# Protoboard_MX2-7-6-ESP12.net
KiCad netlist of a schematic drawn in EAGLE
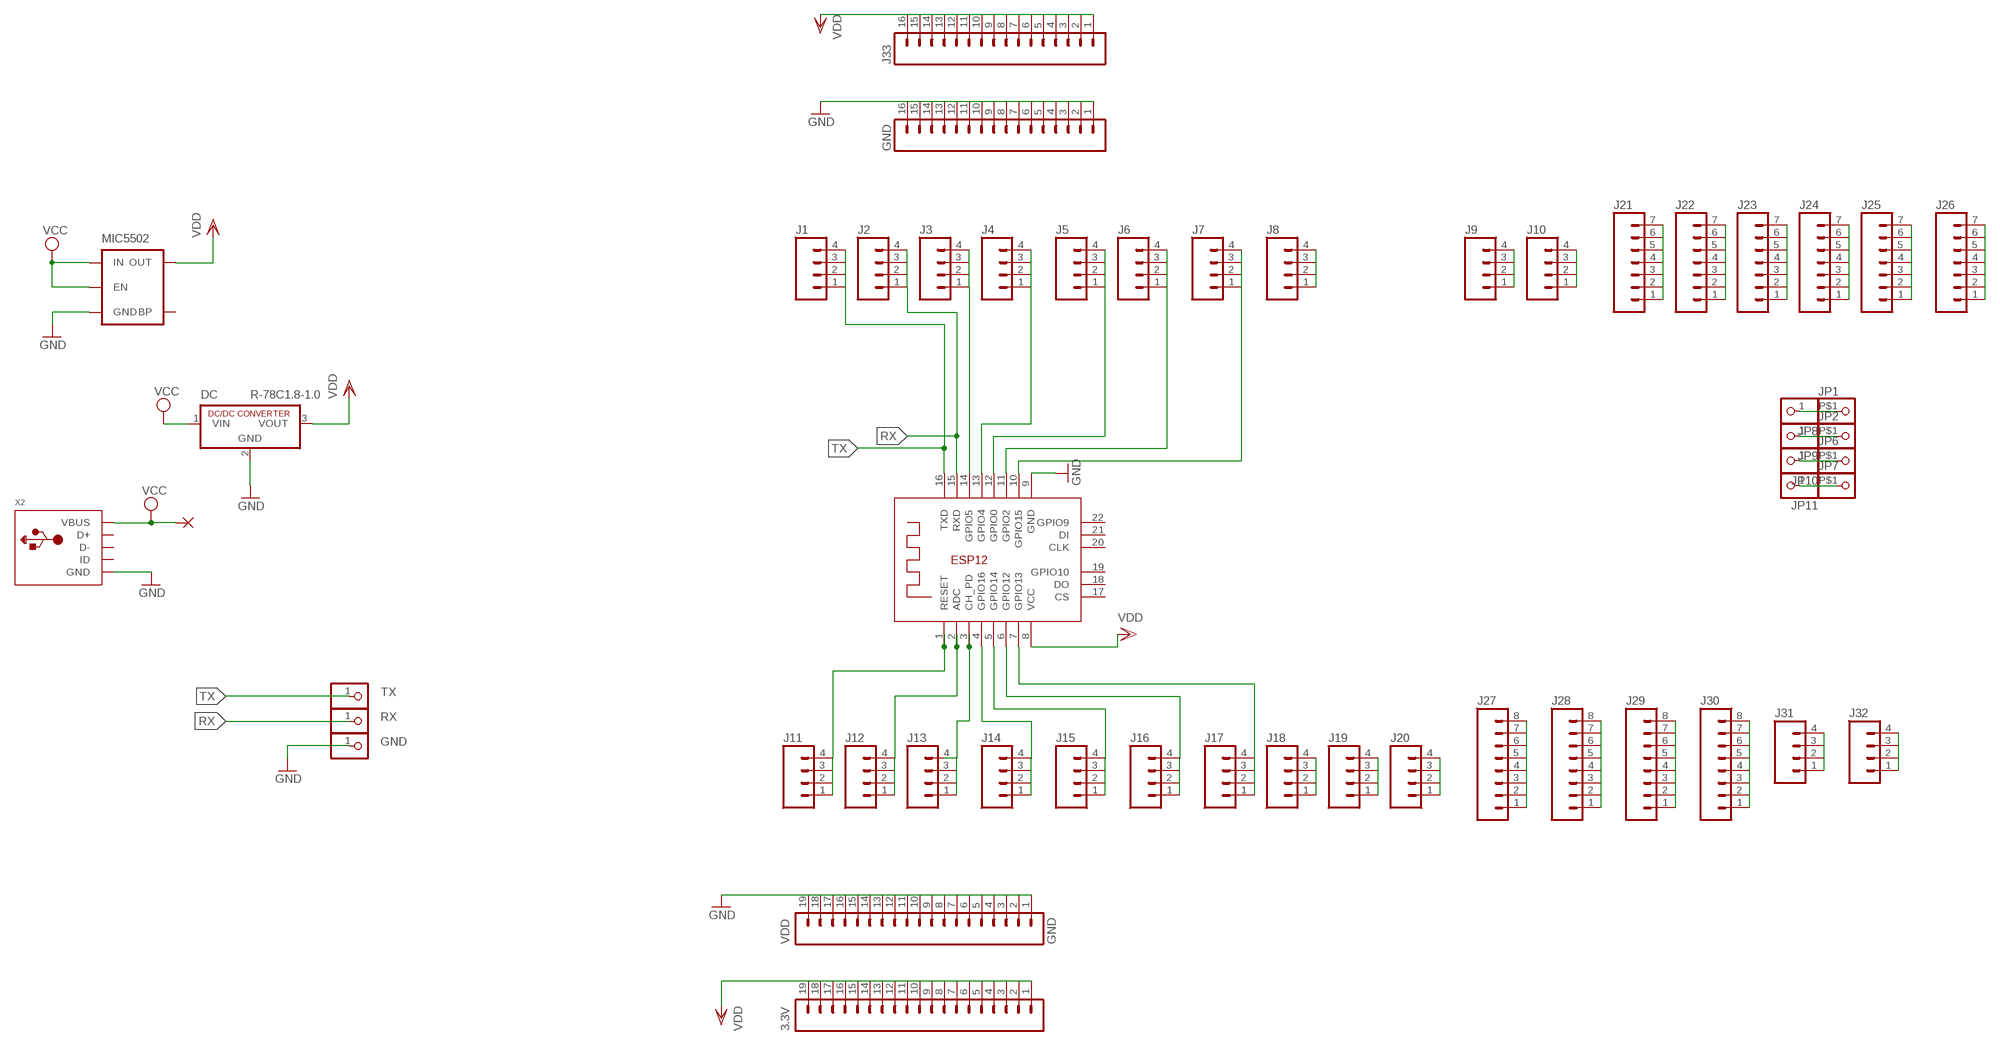
[diagram p0: schematic, sheet 1]

(export (version "E")
  (design (tool "Eeschema 10.0.6"))
  (components
    (comp (ref "3.3V")
      (value "M191X19_NO_SILK")
      (footprint "eagle-import:1X19_NO_SILK")
      (libsource (lib "eagle-import") (part "M191X19_NO_SILK"))
    )
    (comp (ref "5V")
      (value "1,6/0,8")
      (footprint "eagle-import:1,6_0,8")
      (libsource (lib "eagle-import") (part "1,6/0,8"))
    )
    (comp (ref "DC")
      (value "R-78C1.8-1.0")
      (footprint "eagle-import:SIP3")
      (libsource (lib "eagle-import") (part "R-78C-1.01.8"))
    )
    (comp (ref "GND")
      (value "M161X16_NO_SILK")
      (footprint "eagle-import:1X16_NO_SILK")
      (libsource (lib "eagle-import") (part "M161X16_NO_SILK"))
    )
    (comp (ref "J1")
      (value "M04NO_SILK_ALL_ROUND")
      (footprint "eagle-import:1X04_NO_SILK_ALL_ROUND")
      (libsource (lib "eagle-import") (part "M04NO_SILK_ALL_ROUND"))
    )
    (comp (ref "J2")
      (value "M04NO_SILK_ALL_ROUND")
      (footprint "eagle-import:1X04_NO_SILK_ALL_ROUND")
      (libsource (lib "eagle-import") (part "M04NO_SILK_ALL_ROUND"))
    )
    (comp (ref "J3")
      (value "M04NO_SILK_ALL_ROUND")
      (footprint "eagle-import:1X04_NO_SILK_ALL_ROUND")
      (libsource (lib "eagle-import") (part "M04NO_SILK_ALL_ROUND"))
    )
    (comp (ref "J4")
      (value "M04NO_SILK_ALL_ROUND")
      (footprint "eagle-import:1X04_NO_SILK_ALL_ROUND")
      (libsource (lib "eagle-import") (part "M04NO_SILK_ALL_ROUND"))
    )
    (comp (ref "J5")
      (value "M04NO_SILK_ALL_ROUND")
      (footprint "eagle-import:1X04_NO_SILK_ALL_ROUND")
      (libsource (lib "eagle-import") (part "M04NO_SILK_ALL_ROUND"))
    )
    (comp (ref "J6")
      (value "M04NO_SILK_ALL_ROUND")
      (footprint "eagle-import:1X04_NO_SILK_ALL_ROUND")
      (libsource (lib "eagle-import") (part "M04NO_SILK_ALL_ROUND"))
    )
    (comp (ref "J7")
      (value "M04NO_SILK_ALL_ROUND")
      (footprint "eagle-import:1X04_NO_SILK_ALL_ROUND")
      (libsource (lib "eagle-import") (part "M04NO_SILK_ALL_ROUND"))
    )
    (comp (ref "J8")
      (value "M04NO_SILK_ALL_ROUND")
      (footprint "eagle-import:1X04_NO_SILK_ALL_ROUND")
      (libsource (lib "eagle-import") (part "M04NO_SILK_ALL_ROUND"))
    )
    (comp (ref "J9")
      (value "M04NO_SILK_ALL_ROUND")
      (footprint "eagle-import:1X04_NO_SILK_ALL_ROUND")
      (libsource (lib "eagle-import") (part "M04NO_SILK_ALL_ROUND"))
    )
    (comp (ref "J10")
      (value "M04NO_SILK_ALL_ROUND")
      (footprint "eagle-import:1X04_NO_SILK_ALL_ROUND")
      (libsource (lib "eagle-import") (part "M04NO_SILK_ALL_ROUND"))
    )
    (comp (ref "J11")
      (value "M04NO_SILK_ALL_ROUND")
      (footprint "eagle-import:1X04_NO_SILK_ALL_ROUND")
      (libsource (lib "eagle-import") (part "M04NO_SILK_ALL_ROUND"))
    )
    (comp (ref "J12")
      (value "M04NO_SILK_ALL_ROUND")
      (footprint "eagle-import:1X04_NO_SILK_ALL_ROUND")
      (libsource (lib "eagle-import") (part "M04NO_SILK_ALL_ROUND"))
    )
    (comp (ref "J13")
      (value "M04NO_SILK_ALL_ROUND")
      (footprint "eagle-import:1X04_NO_SILK_ALL_ROUND")
      (libsource (lib "eagle-import") (part "M04NO_SILK_ALL_ROUND"))
    )
    (comp (ref "J14")
      (value "M04NO_SILK_ALL_ROUND")
      (footprint "eagle-import:1X04_NO_SILK_ALL_ROUND")
      (libsource (lib "eagle-import") (part "M04NO_SILK_ALL_ROUND"))
    )
    (comp (ref "J15")
      (value "M04NO_SILK_ALL_ROUND")
      (footprint "eagle-import:1X04_NO_SILK_ALL_ROUND")
      (libsource (lib "eagle-import") (part "M04NO_SILK_ALL_ROUND"))
    )
    (comp (ref "J16")
      (value "M04NO_SILK_ALL_ROUND")
      (footprint "eagle-import:1X04_NO_SILK_ALL_ROUND")
      (libsource (lib "eagle-import") (part "M04NO_SILK_ALL_ROUND"))
    )
    (comp (ref "J17")
      (value "M04NO_SILK_ALL_ROUND")
      (footprint "eagle-import:1X04_NO_SILK_ALL_ROUND")
      (libsource (lib "eagle-import") (part "M04NO_SILK_ALL_ROUND"))
    )
    (comp (ref "J18")
      (value "M04NO_SILK_ALL_ROUND")
      (footprint "eagle-import:1X04_NO_SILK_ALL_ROUND")
      (libsource (lib "eagle-import") (part "M04NO_SILK_ALL_ROUND"))
    )
    (comp (ref "J19")
      (value "M04NO_SILK_ALL_ROUND")
      (footprint "eagle-import:1X04_NO_SILK_ALL_ROUND")
      (libsource (lib "eagle-import") (part "M04NO_SILK_ALL_ROUND"))
    )
    (comp (ref "J20")
      (value "M04NO_SILK_ALL_ROUND")
      (footprint "eagle-import:1X04_NO_SILK_ALL_ROUND")
      (libsource (lib "eagle-import") (part "M04NO_SILK_ALL_ROUND"))
    )
    (comp (ref "J21")
      (value "M07NO_SILK")
      (footprint "eagle-import:1X07_NO_SILK")
      (libsource (lib "eagle-import") (part "M07NO_SILK"))
    )
    (comp (ref "J22")
      (value "M07NO_SILK")
      (footprint "eagle-import:1X07_NO_SILK")
      (libsource (lib "eagle-import") (part "M07NO_SILK"))
    )
    (comp (ref "J23")
      (value "M07NO_SILK")
      (footprint "eagle-import:1X07_NO_SILK")
      (libsource (lib "eagle-import") (part "M07NO_SILK"))
    )
    (comp (ref "J24")
      (value "M07NO_SILK")
      (footprint "eagle-import:1X07_NO_SILK")
      (libsource (lib "eagle-import") (part "M07NO_SILK"))
    )
    (comp (ref "J25")
      (value "M07NO_SILK")
      (footprint "eagle-import:1X07_NO_SILK")
      (libsource (lib "eagle-import") (part "M07NO_SILK"))
    )
    (comp (ref "J26")
      (value "M07NO_SILK")
      (footprint "eagle-import:1X07_NO_SILK")
      (libsource (lib "eagle-import") (part "M07NO_SILK"))
    )
    (comp (ref "J27")
      (value "M08NO_SILK_FEMALE_PTH")
      (footprint "eagle-import:1X08_NO_SILK")
      (libsource (lib "eagle-import") (part "M08NO_SILK_FEMALE_PTH"))
    )
    (comp (ref "J28")
      (value "M08NO_SILK_FEMALE_PTH")
      (footprint "eagle-import:1X08_NO_SILK")
      (libsource (lib "eagle-import") (part "M08NO_SILK_FEMALE_PTH"))
    )
    (comp (ref "J29")
      (value "M08NO_SILK_FEMALE_PTH")
      (footprint "eagle-import:1X08_NO_SILK")
      (libsource (lib "eagle-import") (part "M08NO_SILK_FEMALE_PTH"))
    )
    (comp (ref "J30")
      (value "M08NO_SILK_FEMALE_PTH")
      (footprint "eagle-import:1X08_NO_SILK")
      (libsource (lib "eagle-import") (part "M08NO_SILK_FEMALE_PTH"))
    )
    (comp (ref "J31")
      (value "M04NO_SILK_ALL_ROUND")
      (footprint "eagle-import:1X04_NO_SILK_ALL_ROUND")
      (libsource (lib "eagle-import") (part "M04NO_SILK_ALL_ROUND"))
    )
    (comp (ref "J32")
      (value "M04NO_SILK_ALL_ROUND")
      (footprint "eagle-import:1X04_NO_SILK_ALL_ROUND")
      (libsource (lib "eagle-import") (part "M04NO_SILK_ALL_ROUND"))
    )
    (comp (ref "J33")
      (value "M161X16_NO_SILK")
      (footprint "eagle-import:1X16_NO_SILK")
      (libsource (lib "eagle-import") (part "M161X16_NO_SILK"))
    )
    (comp (ref "JP1")
      (value "PINHD-1X1-BIGPOGO")
      (footprint "eagle-import:1X1-BIGPOGO")
      (libsource (lib "eagle-import") (part "PINHD-1X1-BIGPOGO"))
    )
    (comp (ref "JP2")
      (value "PINHD-1X1-BIGPOGO")
      (footprint "eagle-import:1X1-BIGPOGO")
      (libsource (lib "eagle-import") (part "PINHD-1X1-BIGPOGO"))
    )
    (comp (ref "JP3")
      (value "TX")
      (footprint "eagle-import:1X01-CLEANBIG")
      (libsource (lib "eagle-import") (part "PINHD-1X1CB"))
    )
    (comp (ref "JP4")
      (value "RX")
      (footprint "eagle-import:1X01-CLEANBIG")
      (libsource (lib "eagle-import") (part "PINHD-1X1CB"))
    )
    (comp (ref "JP5")
      (value "GND")
      (footprint "eagle-import:1X01-CLEANBIG")
      (libsource (lib "eagle-import") (part "PINHD-1X1CB"))
    )
    (comp (ref "JP6")
      (value "PINHD-1X1-BIGPOGO")
      (footprint "eagle-import:1X1-BIGPOGO")
      (libsource (lib "eagle-import") (part "PINHD-1X1-BIGPOGO"))
    )
    (comp (ref "JP7")
      (value "PINHD-1X1-BIGPOGO")
      (footprint "eagle-import:1X1-BIGPOGO")
      (libsource (lib "eagle-import") (part "PINHD-1X1-BIGPOGO"))
    )
    (comp (ref "JP8")
      (value "PINHD-1X1CB")
      (footprint "eagle-import:1X01-CLEANBIG")
      (libsource (lib "eagle-import") (part "PINHD-1X1CB"))
    )
    (comp (ref "JP9")
      (value "PINHD-1X1CB")
      (footprint "eagle-import:1X01-CLEANBIG")
      (libsource (lib "eagle-import") (part "PINHD-1X1CB"))
    )
    (comp (ref "JP10")
      (value "PINHD-1X1CB")
      (footprint "eagle-import:1X01-CLEANBIG")
      (libsource (lib "eagle-import") (part "PINHD-1X1CB"))
    )
    (comp (ref "JP11")
      (value "PINHD-1X1CB")
      (footprint "eagle-import:1X01-CLEANBIG")
      (libsource (lib "eagle-import") (part "PINHD-1X1CB"))
    )
    (comp (ref "MIC5502")
      (value "MIC52053.3V")
      (footprint "eagle-import:SOT23-5")
      (libsource (lib "eagle-import") (part "MIC52053.3V"))
    )
    (comp (ref "VDD")
      (value "GND")
      (footprint "eagle-import:1X19_NO_SILK")
      (libsource (lib "eagle-import") (part "M191X19_NO_SILK"))
    )
    (comp (ref "X1")
      (value "ESP-12E")
      (footprint "eagle-import:ESP-12E")
      (libsource (lib "eagle-import") (part "ESP-12E"))
    )
    (comp (ref "X2")
      (value "USBMICRO_20329")
      (footprint "eagle-import:4UCONN_20329")
      (libsource (lib "eagle-import") (part "USBMICRO_20329"))
    )
  )
  (nets
    (net (code "1") (name "GND") (class "Default")
      (node (ref "DC") (pin "2") (pinfunction "GND_2") (pintype "passive"))
      (node (ref "GND") (pin "1") (pinfunction "1_1") (pintype "passive"))
      (node (ref "GND") (pin "10") (pinfunction "10_10") (pintype "passive"))
      (node (ref "GND") (pin "11") (pinfunction "11_11") (pintype "passive"))
      (node (ref "GND") (pin "12") (pinfunction "12_12") (pintype "passive"))
      (node (ref "GND") (pin "13") (pinfunction "13_13") (pintype "passive"))
      (node (ref "GND") (pin "14") (pinfunction "14_14") (pintype "passive"))
      (node (ref "GND") (pin "15") (pinfunction "15_15") (pintype "passive"))
      (node (ref "GND") (pin "16") (pinfunction "16_16") (pintype "passive"))
      (node (ref "GND") (pin "2") (pinfunction "2_2") (pintype "passive"))
      (node (ref "GND") (pin "3") (pinfunction "3_3") (pintype "passive"))
      (node (ref "GND") (pin "4") (pinfunction "4_4") (pintype "passive"))
      (node (ref "GND") (pin "5") (pinfunction "5_5") (pintype "passive"))
      (node (ref "GND") (pin "6") (pinfunction "6_6") (pintype "passive"))
      (node (ref "GND") (pin "7") (pinfunction "7_7") (pintype "passive"))
      (node (ref "GND") (pin "8") (pinfunction "8_8") (pintype "passive"))
      (node (ref "GND") (pin "9") (pinfunction "9_9") (pintype "passive"))
      (node (ref "JP5") (pin "1") (pinfunction "1_1") (pintype "passive"))
      (node (ref "MIC5502") (pin "2") (pinfunction "GND_2") (pintype "input"))
      (node (ref "VDD") (pin "1") (pinfunction "1_1") (pintype "passive"))
      (node (ref "VDD") (pin "10") (pinfunction "10_10") (pintype "passive"))
      (node (ref "VDD") (pin "11") (pinfunction "11_11") (pintype "passive"))
      (node (ref "VDD") (pin "12") (pinfunction "12_12") (pintype "passive"))
      (node (ref "VDD") (pin "13") (pinfunction "13_13") (pintype "passive"))
      (node (ref "VDD") (pin "14") (pinfunction "14_14") (pintype "passive"))
      (node (ref "VDD") (pin "15") (pinfunction "15_15") (pintype "passive"))
      (node (ref "VDD") (pin "16") (pinfunction "16_16") (pintype "passive"))
      (node (ref "VDD") (pin "17") (pinfunction "17_17") (pintype "passive"))
      (node (ref "VDD") (pin "18") (pinfunction "18_18") (pintype "passive"))
      (node (ref "VDD") (pin "19") (pinfunction "19_19") (pintype "passive"))
      (node (ref "VDD") (pin "2") (pinfunction "2_2") (pintype "passive"))
      (node (ref "VDD") (pin "3") (pinfunction "3_3") (pintype "passive"))
      (node (ref "VDD") (pin "4") (pinfunction "4_4") (pintype "passive"))
      (node (ref "VDD") (pin "5") (pinfunction "5_5") (pintype "passive"))
      (node (ref "VDD") (pin "6") (pinfunction "6_6") (pintype "passive"))
      (node (ref "VDD") (pin "7") (pinfunction "7_7") (pintype "passive"))
      (node (ref "VDD") (pin "8") (pinfunction "8_8") (pintype "passive"))
      (node (ref "VDD") (pin "9") (pinfunction "9_9") (pintype "passive"))
      (node (ref "X1") (pin "9") (pinfunction "GND_9") (pintype "power_in"))
      (node (ref "X2") (pin "BASE@1") (pinfunction "GND_BASE@1") (pintype "power_in"))
      (node (ref "X2") (pin "BASE@2") (pinfunction "GND_BASE@2") (pintype "power_in"))
      (node (ref "X2") (pin "GND") (pinfunction "GND_GND") (pintype "power_in"))
      (node (ref "X2") (pin "SPRT@1") (pinfunction "GND_SPRT@1") (pintype "power_in"))
      (node (ref "X2") (pin "SPRT@2") (pinfunction "GND_SPRT@2") (pintype "power_in"))
      (node (ref "X2") (pin "SPRT@3") (pinfunction "GND_SPRT@3") (pintype "power_in"))
      (node (ref "X2") (pin "SPRT@4") (pinfunction "GND_SPRT@4") (pintype "power_in"))
    )
    (net (code "2") (name "Net-(J8-Pad1)") (class "Default")
      (node (ref "J8") (pin "1") (pinfunction "1_1") (pintype "passive"))
      (node (ref "J8") (pin "2") (pinfunction "2_2") (pintype "passive"))
      (node (ref "J8") (pin "3") (pinfunction "3_3") (pintype "passive"))
      (node (ref "J8") (pin "4") (pinfunction "4_4") (pintype "passive"))
    )
    (net (code "3") (name "Net-(J9-Pad1)") (class "Default")
      (node (ref "J9") (pin "1") (pinfunction "1_1") (pintype "passive"))
      (node (ref "J9") (pin "2") (pinfunction "2_2") (pintype "passive"))
      (node (ref "J9") (pin "3") (pinfunction "3_3") (pintype "passive"))
      (node (ref "J9") (pin "4") (pinfunction "4_4") (pintype "passive"))
    )
    (net (code "4") (name "Net-(J10-Pad1)") (class "Default")
      (node (ref "J10") (pin "1") (pinfunction "1_1") (pintype "passive"))
      (node (ref "J10") (pin "2") (pinfunction "2_2") (pintype "passive"))
      (node (ref "J10") (pin "3") (pinfunction "3_3") (pintype "passive"))
      (node (ref "J10") (pin "4") (pinfunction "4_4") (pintype "passive"))
    )
    (net (code "5") (name "Net-(J18-Pad1)") (class "Default")
      (node (ref "J18") (pin "1") (pinfunction "1_1") (pintype "passive"))
      (node (ref "J18") (pin "2") (pinfunction "2_2") (pintype "passive"))
      (node (ref "J18") (pin "3") (pinfunction "3_3") (pintype "passive"))
      (node (ref "J18") (pin "4") (pinfunction "4_4") (pintype "passive"))
    )
    (net (code "6") (name "Net-(J19-Pad1)") (class "Default")
      (node (ref "J19") (pin "1") (pinfunction "1_1") (pintype "passive"))
      (node (ref "J19") (pin "2") (pinfunction "2_2") (pintype "passive"))
      (node (ref "J19") (pin "3") (pinfunction "3_3") (pintype "passive"))
      (node (ref "J19") (pin "4") (pinfunction "4_4") (pintype "passive"))
    )
    (net (code "7") (name "Net-(J20-Pad1)") (class "Default")
      (node (ref "J20") (pin "1") (pinfunction "1_1") (pintype "passive"))
      (node (ref "J20") (pin "2") (pinfunction "2_2") (pintype "passive"))
      (node (ref "J20") (pin "3") (pinfunction "3_3") (pintype "passive"))
      (node (ref "J20") (pin "4") (pinfunction "4_4") (pintype "passive"))
    )
    (net (code "8") (name "Net-(J21-Pad1)") (class "Default")
      (node (ref "J21") (pin "1") (pinfunction "1_1") (pintype "passive"))
      (node (ref "J21") (pin "2") (pinfunction "2_2") (pintype "passive"))
      (node (ref "J21") (pin "3") (pinfunction "3_3") (pintype "passive"))
      (node (ref "J21") (pin "4") (pinfunction "4_4") (pintype "passive"))
      (node (ref "J21") (pin "5") (pinfunction "5_5") (pintype "passive"))
      (node (ref "J21") (pin "6") (pinfunction "6_6") (pintype "passive"))
      (node (ref "J21") (pin "7") (pinfunction "7_7") (pintype "passive"))
    )
    (net (code "9") (name "Net-(J22-Pad1)") (class "Default")
      (node (ref "J22") (pin "1") (pinfunction "1_1") (pintype "passive"))
      (node (ref "J22") (pin "2") (pinfunction "2_2") (pintype "passive"))
      (node (ref "J22") (pin "3") (pinfunction "3_3") (pintype "passive"))
      (node (ref "J22") (pin "4") (pinfunction "4_4") (pintype "passive"))
      (node (ref "J22") (pin "5") (pinfunction "5_5") (pintype "passive"))
      (node (ref "J22") (pin "6") (pinfunction "6_6") (pintype "passive"))
      (node (ref "J22") (pin "7") (pinfunction "7_7") (pintype "passive"))
    )
    (net (code "10") (name "Net-(J23-Pad1)") (class "Default")
      (node (ref "J23") (pin "1") (pinfunction "1_1") (pintype "passive"))
      (node (ref "J23") (pin "2") (pinfunction "2_2") (pintype "passive"))
      (node (ref "J23") (pin "3") (pinfunction "3_3") (pintype "passive"))
      (node (ref "J23") (pin "4") (pinfunction "4_4") (pintype "passive"))
      (node (ref "J23") (pin "5") (pinfunction "5_5") (pintype "passive"))
      (node (ref "J23") (pin "6") (pinfunction "6_6") (pintype "passive"))
      (node (ref "J23") (pin "7") (pinfunction "7_7") (pintype "passive"))
    )
    (net (code "11") (name "Net-(J24-Pad1)") (class "Default")
      (node (ref "J24") (pin "1") (pinfunction "1_1") (pintype "passive"))
      (node (ref "J24") (pin "2") (pinfunction "2_2") (pintype "passive"))
      (node (ref "J24") (pin "3") (pinfunction "3_3") (pintype "passive"))
      (node (ref "J24") (pin "4") (pinfunction "4_4") (pintype "passive"))
      (node (ref "J24") (pin "5") (pinfunction "5_5") (pintype "passive"))
      (node (ref "J24") (pin "6") (pinfunction "6_6") (pintype "passive"))
      (node (ref "J24") (pin "7") (pinfunction "7_7") (pintype "passive"))
    )
    (net (code "12") (name "Net-(J25-Pad1)") (class "Default")
      (node (ref "J25") (pin "1") (pinfunction "1_1") (pintype "passive"))
      (node (ref "J25") (pin "2") (pinfunction "2_2") (pintype "passive"))
      (node (ref "J25") (pin "3") (pinfunction "3_3") (pintype "passive"))
      (node (ref "J25") (pin "4") (pinfunction "4_4") (pintype "passive"))
      (node (ref "J25") (pin "5") (pinfunction "5_5") (pintype "passive"))
      (node (ref "J25") (pin "6") (pinfunction "6_6") (pintype "passive"))
      (node (ref "J25") (pin "7") (pinfunction "7_7") (pintype "passive"))
    )
    (net (code "13") (name "Net-(J26-Pad1)") (class "Default")
      (node (ref "J26") (pin "1") (pinfunction "1_1") (pintype "passive"))
      (node (ref "J26") (pin "2") (pinfunction "2_2") (pintype "passive"))
      (node (ref "J26") (pin "3") (pinfunction "3_3") (pintype "passive"))
      (node (ref "J26") (pin "4") (pinfunction "4_4") (pintype "passive"))
      (node (ref "J26") (pin "5") (pinfunction "5_5") (pintype "passive"))
      (node (ref "J26") (pin "6") (pinfunction "6_6") (pintype "passive"))
      (node (ref "J26") (pin "7") (pinfunction "7_7") (pintype "passive"))
    )
    (net (code "14") (name "Net-(J27-Pad1)") (class "Default")
      (node (ref "J27") (pin "1") (pinfunction "1_1") (pintype "passive"))
      (node (ref "J27") (pin "2") (pinfunction "2_2") (pintype "passive"))
      (node (ref "J27") (pin "3") (pinfunction "3_3") (pintype "passive"))
      (node (ref "J27") (pin "4") (pinfunction "4_4") (pintype "passive"))
      (node (ref "J27") (pin "5") (pinfunction "5_5") (pintype "passive"))
      (node (ref "J27") (pin "6") (pinfunction "6_6") (pintype "passive"))
      (node (ref "J27") (pin "7") (pinfunction "7_7") (pintype "passive"))
      (node (ref "J27") (pin "8") (pinfunction "8_8") (pintype "passive"))
    )
    (net (code "15") (name "Net-(J28-Pad1)") (class "Default")
      (node (ref "J28") (pin "1") (pinfunction "1_1") (pintype "passive"))
      (node (ref "J28") (pin "2") (pinfunction "2_2") (pintype "passive"))
      (node (ref "J28") (pin "3") (pinfunction "3_3") (pintype "passive"))
      (node (ref "J28") (pin "4") (pinfunction "4_4") (pintype "passive"))
      (node (ref "J28") (pin "5") (pinfunction "5_5") (pintype "passive"))
      (node (ref "J28") (pin "6") (pinfunction "6_6") (pintype "passive"))
      (node (ref "J28") (pin "7") (pinfunction "7_7") (pintype "passive"))
      (node (ref "J28") (pin "8") (pinfunction "8_8") (pintype "passive"))
    )
    (net (code "16") (name "Net-(J29-Pad1)") (class "Default")
      (node (ref "J29") (pin "1") (pinfunction "1_1") (pintype "passive"))
      (node (ref "J29") (pin "2") (pinfunction "2_2") (pintype "passive"))
      (node (ref "J29") (pin "3") (pinfunction "3_3") (pintype "passive"))
      (node (ref "J29") (pin "4") (pinfunction "4_4") (pintype "passive"))
      (node (ref "J29") (pin "5") (pinfunction "5_5") (pintype "passive"))
      (node (ref "J29") (pin "6") (pinfunction "6_6") (pintype "passive"))
      (node (ref "J29") (pin "7") (pinfunction "7_7") (pintype "passive"))
      (node (ref "J29") (pin "8") (pinfunction "8_8") (pintype "passive"))
    )
    (net (code "17") (name "Net-(J30-Pad1)") (class "Default")
      (node (ref "J30") (pin "1") (pinfunction "1_1") (pintype "passive"))
      (node (ref "J30") (pin "2") (pinfunction "2_2") (pintype "passive"))
      (node (ref "J30") (pin "3") (pinfunction "3_3") (pintype "passive"))
      (node (ref "J30") (pin "4") (pinfunction "4_4") (pintype "passive"))
      (node (ref "J30") (pin "5") (pinfunction "5_5") (pintype "passive"))
      (node (ref "J30") (pin "6") (pinfunction "6_6") (pintype "passive"))
      (node (ref "J30") (pin "7") (pinfunction "7_7") (pintype "passive"))
      (node (ref "J30") (pin "8") (pinfunction "8_8") (pintype "passive"))
    )
    (net (code "18") (name "Net-(J31-Pad1)") (class "Default")
      (node (ref "J31") (pin "1") (pinfunction "1_1") (pintype "passive"))
      (node (ref "J31") (pin "2") (pinfunction "2_2") (pintype "passive"))
      (node (ref "J31") (pin "3") (pinfunction "3_3") (pintype "passive"))
      (node (ref "J31") (pin "4") (pinfunction "4_4") (pintype "passive"))
    )
    (net (code "19") (name "Net-(J32-Pad1)") (class "Default")
      (node (ref "J32") (pin "1") (pinfunction "1_1") (pintype "passive"))
      (node (ref "J32") (pin "2") (pinfunction "2_2") (pintype "passive"))
      (node (ref "J32") (pin "3") (pinfunction "3_3") (pintype "passive"))
      (node (ref "J32") (pin "4") (pinfunction "4_4") (pintype "passive"))
    )
    (net (code "20") (name "Net-(JP1-1)") (class "Default")
      (node (ref "JP1") (pin "P$1") (pinfunction "1_P$1") (pintype "passive"))
      (node (ref "JP8") (pin "1") (pinfunction "1_1") (pintype "passive"))
    )
    (net (code "21") (name "Net-(JP2-1)") (class "Default")
      (node (ref "JP2") (pin "P$1") (pinfunction "1_P$1") (pintype "passive"))
      (node (ref "JP9") (pin "1") (pinfunction "1_1") (pintype "passive"))
    )
    (net (code "22") (name "Net-(JP6-1)") (class "Default")
      (node (ref "JP10") (pin "1") (pinfunction "1_1") (pintype "passive"))
      (node (ref "JP6") (pin "P$1") (pinfunction "1_P$1") (pintype "passive"))
    )
    (net (code "23") (name "Net-(JP7-1)") (class "Default")
      (node (ref "JP11") (pin "1") (pinfunction "1_1") (pintype "passive"))
      (node (ref "JP7") (pin "P$1") (pinfunction "1_P$1") (pintype "passive"))
    )
    (net (code "24") (name "Net-(X1-ADC)") (class "Default")
      (node (ref "J12") (pin "1") (pinfunction "1_1") (pintype "passive"))
      (node (ref "J12") (pin "2") (pinfunction "2_2") (pintype "passive"))
      (node (ref "J12") (pin "3") (pinfunction "3_3") (pintype "passive"))
      (node (ref "J12") (pin "4") (pinfunction "4_4") (pintype "passive"))
      (node (ref "X1") (pin "2") (pinfunction "ADC_2") (pintype "passive"))
    )
    (net (code "25") (name "Net-(X1-CH_PD)") (class "Default")
      (node (ref "J13") (pin "1") (pinfunction "1_1") (pintype "passive"))
      (node (ref "J13") (pin "2") (pinfunction "2_2") (pintype "passive"))
      (node (ref "J13") (pin "3") (pinfunction "3_3") (pintype "passive"))
      (node (ref "J13") (pin "4") (pinfunction "4_4") (pintype "passive"))
      (node (ref "X1") (pin "3") (pinfunction "CH_PD_3") (pintype "input"))
    )
    (net (code "26") (name "Net-(X1-GPIO0)") (class "Default")
      (node (ref "J5") (pin "1") (pinfunction "1_1") (pintype "passive"))
      (node (ref "J5") (pin "2") (pinfunction "2_2") (pintype "passive"))
      (node (ref "J5") (pin "3") (pinfunction "3_3") (pintype "passive"))
      (node (ref "J5") (pin "4") (pinfunction "4_4") (pintype "passive"))
      (node (ref "X1") (pin "12") (pinfunction "GPIO0_12") (pintype "bidirectional"))
    )
    (net (code "27") (name "Net-(X1-GPIO2)") (class "Default")
      (node (ref "J6") (pin "1") (pinfunction "1_1") (pintype "passive"))
      (node (ref "J6") (pin "2") (pinfunction "2_2") (pintype "passive"))
      (node (ref "J6") (pin "3") (pinfunction "3_3") (pintype "passive"))
      (node (ref "J6") (pin "4") (pinfunction "4_4") (pintype "passive"))
      (node (ref "X1") (pin "11") (pinfunction "GPIO2_11") (pintype "bidirectional"))
    )
    (net (code "28") (name "Net-(X1-GPIO4)") (class "Default")
      (node (ref "J4") (pin "1") (pinfunction "1_1") (pintype "passive"))
      (node (ref "J4") (pin "2") (pinfunction "2_2") (pintype "passive"))
      (node (ref "J4") (pin "3") (pinfunction "3_3") (pintype "passive"))
      (node (ref "J4") (pin "4") (pinfunction "4_4") (pintype "passive"))
      (node (ref "X1") (pin "13") (pinfunction "GPIO4_13") (pintype "bidirectional"))
    )
    (net (code "29") (name "Net-(X1-GPIO5)") (class "Default")
      (node (ref "J3") (pin "1") (pinfunction "1_1") (pintype "passive"))
      (node (ref "J3") (pin "2") (pinfunction "2_2") (pintype "passive"))
      (node (ref "J3") (pin "3") (pinfunction "3_3") (pintype "passive"))
      (node (ref "J3") (pin "4") (pinfunction "4_4") (pintype "passive"))
      (node (ref "X1") (pin "14") (pinfunction "GPIO5_14") (pintype "bidirectional"))
    )
    (net (code "30") (name "Net-(X1-GPIO12)") (class "Default")
      (node (ref "J16") (pin "1") (pinfunction "1_1") (pintype "passive"))
      (node (ref "J16") (pin "2") (pinfunction "2_2") (pintype "passive"))
      (node (ref "J16") (pin "3") (pinfunction "3_3") (pintype "passive"))
      (node (ref "J16") (pin "4") (pinfunction "4_4") (pintype "passive"))
      (node (ref "X1") (pin "6") (pinfunction "GPIO12_6") (pintype "bidirectional"))
    )
    (net (code "31") (name "Net-(X1-GPIO13)") (class "Default")
      (node (ref "J17") (pin "1") (pinfunction "1_1") (pintype "passive"))
      (node (ref "J17") (pin "2") (pinfunction "2_2") (pintype "passive"))
      (node (ref "J17") (pin "3") (pinfunction "3_3") (pintype "passive"))
      (node (ref "J17") (pin "4") (pinfunction "4_4") (pintype "passive"))
      (node (ref "X1") (pin "7") (pinfunction "GPIO13_7") (pintype "bidirectional"))
    )
    (net (code "32") (name "Net-(X1-GPIO14)") (class "Default")
      (node (ref "J15") (pin "1") (pinfunction "1_1") (pintype "passive"))
      (node (ref "J15") (pin "2") (pinfunction "2_2") (pintype "passive"))
      (node (ref "J15") (pin "3") (pinfunction "3_3") (pintype "passive"))
      (node (ref "J15") (pin "4") (pinfunction "4_4") (pintype "passive"))
      (node (ref "X1") (pin "5") (pinfunction "GPIO14_5") (pintype "bidirectional"))
    )
    (net (code "33") (name "Net-(X1-GPIO15)") (class "Default")
      (node (ref "J7") (pin "1") (pinfunction "1_1") (pintype "passive"))
      (node (ref "J7") (pin "2") (pinfunction "2_2") (pintype "passive"))
      (node (ref "J7") (pin "3") (pinfunction "3_3") (pintype "passive"))
      (node (ref "J7") (pin "4") (pinfunction "4_4") (pintype "passive"))
      (node (ref "X1") (pin "10") (pinfunction "GPIO15_10") (pintype "bidirectional"))
    )
    (net (code "34") (name "Net-(X1-GPIO16)") (class "Default")
      (node (ref "J14") (pin "1") (pinfunction "1_1") (pintype "passive"))
      (node (ref "J14") (pin "2") (pinfunction "2_2") (pintype "passive"))
      (node (ref "J14") (pin "3") (pinfunction "3_3") (pintype "passive"))
      (node (ref "J14") (pin "4") (pinfunction "4_4") (pintype "passive"))
      (node (ref "X1") (pin "4") (pinfunction "GPIO16_4") (pintype "bidirectional"))
    )
    (net (code "35") (name "Net-(X1-RESET)") (class "Default")
      (node (ref "J11") (pin "1") (pinfunction "1_1") (pintype "passive"))
      (node (ref "J11") (pin "2") (pinfunction "2_2") (pintype "passive"))
      (node (ref "J11") (pin "3") (pinfunction "3_3") (pintype "passive"))
      (node (ref "J11") (pin "4") (pinfunction "4_4") (pintype "passive"))
      (node (ref "X1") (pin "1") (pinfunction "RESET_1") (pintype "input"))
    )
    (net (code "36") (name "RX") (class "Default")
      (node (ref "J2") (pin "1") (pinfunction "1_1") (pintype "passive"))
      (node (ref "J2") (pin "2") (pinfunction "2_2") (pintype "passive"))
      (node (ref "J2") (pin "3") (pinfunction "3_3") (pintype "passive"))
      (node (ref "J2") (pin "4") (pinfunction "4_4") (pintype "passive"))
      (node (ref "JP4") (pin "1") (pinfunction "1_1") (pintype "passive"))
      (node (ref "X1") (pin "15") (pinfunction "RXD_15") (pintype "input"))
    )
    (net (code "37") (name "TX") (class "Default")
      (node (ref "J1") (pin "1") (pinfunction "1_1") (pintype "passive"))
      (node (ref "J1") (pin "2") (pinfunction "2_2") (pintype "passive"))
      (node (ref "J1") (pin "3") (pinfunction "3_3") (pintype "passive"))
      (node (ref "J1") (pin "4") (pinfunction "4_4") (pintype "passive"))
      (node (ref "JP3") (pin "1") (pinfunction "1_1") (pintype "passive"))
      (node (ref "X1") (pin "16") (pinfunction "TXD_16") (pintype "output"))
    )
    (net (code "38") (name "VCC") (class "Default")
      (node (ref "5V") (pin "1") (pinfunction "P_1") (pintype "passive"))
      (node (ref "DC") (pin "1") (pinfunction "VIN_1") (pintype "passive"))
      (node (ref "MIC5502") (pin "1") (pinfunction "IN_1") (pintype "input"))
      (node (ref "MIC5502") (pin "3") (pinfunction "EN_3") (pintype "input"))
      (node (ref "X2") (pin "VBUS") (pinfunction "VBUS_VBUS") (pintype "power_in"))
    )
    (net (code "39") (name "VDD") (class "Default")
      (node (ref "3.3V") (pin "1") (pinfunction "1_1") (pintype "passive"))
      (node (ref "3.3V") (pin "10") (pinfunction "10_10") (pintype "passive"))
      (node (ref "3.3V") (pin "11") (pinfunction "11_11") (pintype "passive"))
      (node (ref "3.3V") (pin "12") (pinfunction "12_12") (pintype "passive"))
      (node (ref "3.3V") (pin "13") (pinfunction "13_13") (pintype "passive"))
      (node (ref "3.3V") (pin "14") (pinfunction "14_14") (pintype "passive"))
      (node (ref "3.3V") (pin "15") (pinfunction "15_15") (pintype "passive"))
      (node (ref "3.3V") (pin "16") (pinfunction "16_16") (pintype "passive"))
      (node (ref "3.3V") (pin "17") (pinfunction "17_17") (pintype "passive"))
      (node (ref "3.3V") (pin "18") (pinfunction "18_18") (pintype "passive"))
      (node (ref "3.3V") (pin "19") (pinfunction "19_19") (pintype "passive"))
      (node (ref "3.3V") (pin "2") (pinfunction "2_2") (pintype "passive"))
      (node (ref "3.3V") (pin "3") (pinfunction "3_3") (pintype "passive"))
      (node (ref "3.3V") (pin "4") (pinfunction "4_4") (pintype "passive"))
      (node (ref "3.3V") (pin "5") (pinfunction "5_5") (pintype "passive"))
      (node (ref "3.3V") (pin "6") (pinfunction "6_6") (pintype "passive"))
      (node (ref "3.3V") (pin "7") (pinfunction "7_7") (pintype "passive"))
      (node (ref "3.3V") (pin "8") (pinfunction "8_8") (pintype "passive"))
      (node (ref "3.3V") (pin "9") (pinfunction "9_9") (pintype "passive"))
      (node (ref "DC") (pin "3") (pinfunction "VOUT_3") (pintype "passive"))
      (node (ref "J33") (pin "1") (pinfunction "1_1") (pintype "passive"))
      (node (ref "J33") (pin "10") (pinfunction "10_10") (pintype "passive"))
      (node (ref "J33") (pin "11") (pinfunction "11_11") (pintype "passive"))
      (node (ref "J33") (pin "12") (pinfunction "12_12") (pintype "passive"))
      (node (ref "J33") (pin "13") (pinfunction "13_13") (pintype "passive"))
      (node (ref "J33") (pin "14") (pinfunction "14_14") (pintype "passive"))
      (node (ref "J33") (pin "15") (pinfunction "15_15") (pintype "passive"))
      (node (ref "J33") (pin "16") (pinfunction "16_16") (pintype "passive"))
      (node (ref "J33") (pin "2") (pinfunction "2_2") (pintype "passive"))
      (node (ref "J33") (pin "3") (pinfunction "3_3") (pintype "passive"))
      (node (ref "J33") (pin "4") (pinfunction "4_4") (pintype "passive"))
      (node (ref "J33") (pin "5") (pinfunction "5_5") (pintype "passive"))
      (node (ref "J33") (pin "6") (pinfunction "6_6") (pintype "passive"))
      (node (ref "J33") (pin "7") (pinfunction "7_7") (pintype "passive"))
      (node (ref "J33") (pin "8") (pinfunction "8_8") (pintype "passive"))
      (node (ref "J33") (pin "9") (pinfunction "9_9") (pintype "passive"))
      (node (ref "MIC5502") (pin "5") (pinfunction "OUT_5") (pintype "passive"))
      (node (ref "X1") (pin "8") (pinfunction "VCC_8") (pintype "power_in"))
    )
    (net (code "40") (name "unconnected-(MIC5502-BP-Pad4)") (class "Default")
      (node (ref "MIC5502") (pin "4") (pinfunction "BP_4") (pintype "input"))
    )
    (net (code "41") (name "unconnected-(X1-CLK-Pad20)") (class "Default")
      (node (ref "X1") (pin "20") (pinfunction "CLK_20") (pintype "bidirectional"))
    )
    (net (code "42") (name "unconnected-(X1-CS-Pad17)") (class "Default")
      (node (ref "X1") (pin "17") (pinfunction "CS_17") (pintype "bidirectional"))
    )
    (net (code "43") (name "unconnected-(X1-DI-Pad21)") (class "Default")
      (node (ref "X1") (pin "21") (pinfunction "DI_21") (pintype "bidirectional"))
    )
    (net (code "44") (name "unconnected-(X1-DO-Pad18)") (class "Default")
      (node (ref "X1") (pin "18") (pinfunction "DO_18") (pintype "bidirectional"))
    )
    (net (code "45") (name "unconnected-(X1-GPIO9-Pad22)") (class "Default")
      (node (ref "X1") (pin "22") (pinfunction "GPIO9_22") (pintype "bidirectional"))
    )
    (net (code "46") (name "unconnected-(X1-GPIO10-Pad19)") (class "Default")
      (node (ref "X1") (pin "19") (pinfunction "GPIO10_19") (pintype "bidirectional"))
    )
    (net (code "47") (name "unconnected-(X2-PadD+)") (class "Default")
      (node (ref "X2") (pin "D+") (pinfunction "D+_D+") (pintype "bidirectional"))
    )
    (net (code "48") (name "unconnected-(X2-PadD-)") (class "Default")
      (node (ref "X2") (pin "D-") (pinfunction "D-_D-") (pintype "bidirectional"))
    )
    (net (code "49") (name "unconnected-(X2-PadID)") (class "Default")
      (node (ref "X2") (pin "ID") (pinfunction "ID_ID") (pintype "bidirectional"))
    )
  )
)
